# LeftHandPath_Controls.net
KiCad netlist of a schematic drawn in EAGLE
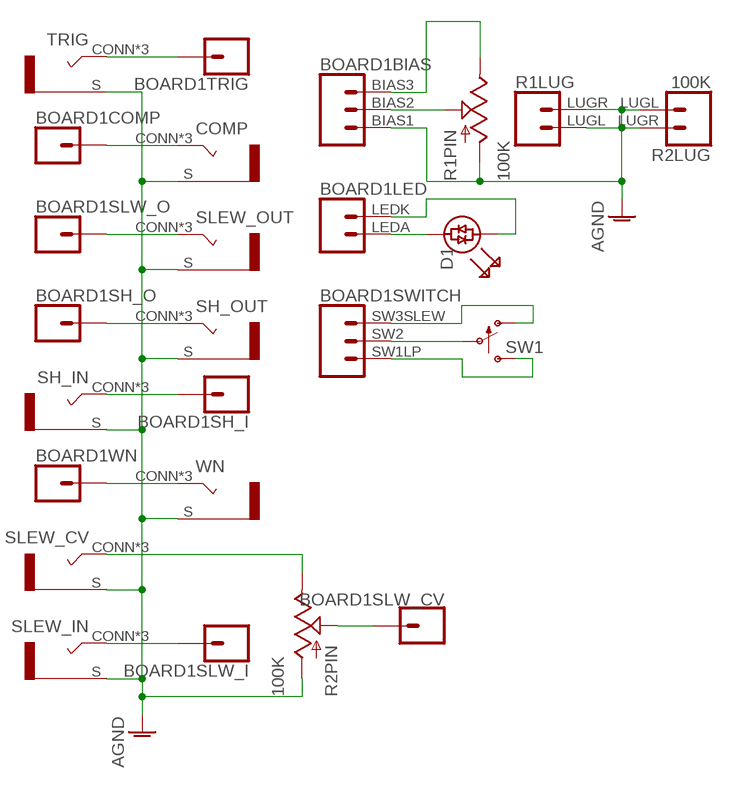
[diagram p0: schematic, sheet 1]

(export (version "E")
  (design (tool "Eeschema 10.0.6"))
  (components
    (comp (ref "BOARD1")
      (value "TLHPFOC_LINK")
      (footprint "eagle-import:TLHPFOC")
      (libsource (lib "eagle-import") (part "TLHPFOC_LINK"))
    )
    (comp (ref "COMP")
      (value "COMBI-JACKCINCHNANA")
      (footprint "eagle-import:NEWCOMBOJACK_PANEL")
      (libsource (lib "eagle-import") (part "COMBI-JACKCINCHNANA"))
    )
    (comp (ref "D1")
      (value "5MM_BICOLOUR_LED")
      (footprint "eagle-import:LED5MM")
      (libsource (lib "eagle-import") (part "5MM_BICOLOUR_LED"))
    )
    (comp (ref "R1")
      (value "100K")
      (footprint "eagle-import:ALPHA_RV09_9MMPOT")
      (libsource (lib "eagle-import") (part "POTENTIOMETER"))
    )
    (comp (ref "R2")
      (value "100K")
      (footprint "eagle-import:ALPHA_RV09_9MMPOT")
      (libsource (lib "eagle-import") (part "POTENTIOMETER"))
    )
    (comp (ref "SH_IN")
      (value "COMBI-JACKCINCHNANA")
      (footprint "eagle-import:NEWCOMBOJACK_PANEL")
      (libsource (lib "eagle-import") (part "COMBI-JACKCINCHNANA"))
    )
    (comp (ref "SH_OUT")
      (value "COMBI-JACKCINCHNANA")
      (footprint "eagle-import:NEWCOMBOJACK_PANEL")
      (libsource (lib "eagle-import") (part "COMBI-JACKCINCHNANA"))
    )
    (comp (ref "SLEW_CV")
      (value "COMBI-JACKCINCHNANA")
      (footprint "eagle-import:NEWCOMBOJACK_PANEL")
      (libsource (lib "eagle-import") (part "COMBI-JACKCINCHNANA"))
    )
    (comp (ref "SLEW_IN")
      (value "COMBI-JACKCINCHNANA")
      (footprint "eagle-import:NEWCOMBOJACK_PANEL")
      (libsource (lib "eagle-import") (part "COMBI-JACKCINCHNANA"))
    )
    (comp (ref "SLEW_OUT")
      (value "COMBI-JACKCINCHNANA")
      (footprint "eagle-import:NEWCOMBOJACK_PANEL")
      (libsource (lib "eagle-import") (part "COMBI-JACKCINCHNANA"))
    )
    (comp (ref "SW1")
      (value "SPDT_SWITCHDW1")
      (footprint "eagle-import:MICRODPDT-DW1")
      (libsource (lib "eagle-import") (part "SPDT_SWITCHDW1"))
    )
    (comp (ref "TRIG")
      (value "COMBI-JACKCINCHNANA")
      (footprint "eagle-import:NEWCOMBOJACK_PANEL")
      (libsource (lib "eagle-import") (part "COMBI-JACKCINCHNANA"))
    )
    (comp (ref "WN")
      (value "COMBI-JACKCINCHNANA")
      (footprint "eagle-import:NEWCOMBOJACK_PANEL")
      (libsource (lib "eagle-import") (part "COMBI-JACKCINCHNANA"))
    )
  )
  (nets
    (net (code "1") (name "AGND") (class "Default")
      (node (ref "BOARD1") (pin "BIAS1") (pinfunction "1_BIAS1") (pintype "passive"))
      (node (ref "COMP") (pin "S") (pinfunction "S_S") (pintype "passive"))
      (node (ref "R1") (pin "C1") (pinfunction "A_C1") (pintype "passive"))
      (node (ref "R1") (pin "LUGL") (pinfunction "1_LUGL") (pintype "passive"))
      (node (ref "R1") (pin "LUGR") (pinfunction "2_LUGR") (pintype "passive"))
      (node (ref "R2") (pin "C1") (pinfunction "A_C1") (pintype "passive"))
      (node (ref "R2") (pin "LUGL") (pinfunction "1_LUGL") (pintype "passive"))
      (node (ref "R2") (pin "LUGR") (pinfunction "2_LUGR") (pintype "passive"))
      (node (ref "SH_IN") (pin "S") (pinfunction "S_S") (pintype "passive"))
      (node (ref "SH_OUT") (pin "S") (pinfunction "S_S") (pintype "passive"))
      (node (ref "SLEW_CV") (pin "S") (pinfunction "S_S") (pintype "passive"))
      (node (ref "SLEW_IN") (pin "S") (pinfunction "S_S") (pintype "passive"))
      (node (ref "SLEW_OUT") (pin "S") (pinfunction "S_S") (pintype "passive"))
      (node (ref "TRIG") (pin "S") (pinfunction "S_S") (pintype "passive"))
      (node (ref "WN") (pin "S") (pinfunction "S_S") (pintype "passive"))
    )
    (net (code "2") (name "Net-(BOARD1A-2)") (class "Default")
      (node (ref "BOARD1") (pin "BIAS2") (pinfunction "2_BIAS2") (pintype "passive"))
      (node (ref "R1") (pin "C2") (pinfunction "W_C2") (pintype "passive"))
    )
    (net (code "3") (name "Net-(BOARD1A-3)") (class "Default")
      (node (ref "BOARD1") (pin "BIAS3") (pinfunction "3_BIAS3") (pintype "passive"))
      (node (ref "R1") (pin "C3") (pinfunction "B_C3") (pintype "passive"))
    )
    (net (code "4") (name "Net-(BOARD1B-1)") (class "Default")
      (node (ref "BOARD1") (pin "COMP") (pinfunction "1_COMP") (pintype "passive"))
      (node (ref "COMP") (pin "CONN") (pinfunction "T_CONN") (pintype "passive"))
      (node (ref "COMP") (pin "T1") (pinfunction "T_T1") (pintype "passive"))
      (node (ref "COMP") (pin "T2") (pinfunction "T_T2") (pintype "passive"))
    )
    (net (code "5") (name "Net-(BOARD1C-1)") (class "Default")
      (node (ref "BOARD1") (pin "LEDA") (pinfunction "1_LEDA") (pintype "passive"))
      (node (ref "D1") (pin "A") (pinfunction "AN_A") (pintype "input"))
    )
    (net (code "6") (name "Net-(BOARD1C-2)") (class "Default")
      (node (ref "BOARD1") (pin "LEDK") (pinfunction "2_LEDK") (pintype "passive"))
      (node (ref "D1") (pin "K") (pinfunction "KA_K") (pintype "output"))
    )
    (net (code "7") (name "Net-(BOARD1D-1)") (class "Default")
      (node (ref "BOARD1") (pin "SH_I") (pinfunction "1_SH_I") (pintype "passive"))
      (node (ref "SH_IN") (pin "CONN") (pinfunction "T_CONN") (pintype "passive"))
      (node (ref "SH_IN") (pin "T1") (pinfunction "T_T1") (pintype "passive"))
      (node (ref "SH_IN") (pin "T2") (pinfunction "T_T2") (pintype "passive"))
    )
    (net (code "8") (name "Net-(BOARD1E-1)") (class "Default")
      (node (ref "BOARD1") (pin "SH_O") (pinfunction "1_SH_O") (pintype "passive"))
      (node (ref "SH_OUT") (pin "CONN") (pinfunction "T_CONN") (pintype "passive"))
      (node (ref "SH_OUT") (pin "T1") (pinfunction "T_T1") (pintype "passive"))
      (node (ref "SH_OUT") (pin "T2") (pinfunction "T_T2") (pintype "passive"))
    )
    (net (code "9") (name "Net-(BOARD1F-1)") (class "Default")
      (node (ref "BOARD1") (pin "SLW_CV") (pinfunction "1_SLW_CV") (pintype "passive"))
      (node (ref "R2") (pin "C2") (pinfunction "W_C2") (pintype "passive"))
    )
    (net (code "10") (name "Net-(BOARD1G-1)") (class "Default")
      (node (ref "BOARD1") (pin "SLW_I") (pinfunction "1_SLW_I") (pintype "passive"))
      (node (ref "SLEW_IN") (pin "CONN") (pinfunction "T_CONN") (pintype "passive"))
      (node (ref "SLEW_IN") (pin "T1") (pinfunction "T_T1") (pintype "passive"))
      (node (ref "SLEW_IN") (pin "T2") (pinfunction "T_T2") (pintype "passive"))
    )
    (net (code "11") (name "Net-(BOARD1H-1)") (class "Default")
      (node (ref "BOARD1") (pin "SLW_O") (pinfunction "1_SLW_O") (pintype "passive"))
      (node (ref "SLEW_OUT") (pin "CONN") (pinfunction "T_CONN") (pintype "passive"))
      (node (ref "SLEW_OUT") (pin "T1") (pinfunction "T_T1") (pintype "passive"))
      (node (ref "SLEW_OUT") (pin "T2") (pinfunction "T_T2") (pintype "passive"))
    )
    (net (code "12") (name "Net-(BOARD1I-1)") (class "Default")
      (node (ref "BOARD1") (pin "SW1LP") (pinfunction "1_SW1LP") (pintype "passive"))
      (node (ref "SW1") (pin "C3") (pinfunction "S_C3") (pintype "passive"))
    )
    (net (code "13") (name "Net-(BOARD1I-2)") (class "Default")
      (node (ref "BOARD1") (pin "SW2") (pinfunction "2_SW2") (pintype "passive"))
      (node (ref "SW1") (pin "C2") (pinfunction "P_C2") (pintype "passive"))
    )
    (net (code "14") (name "Net-(BOARD1I-3)") (class "Default")
      (node (ref "BOARD1") (pin "SW3SLEW") (pinfunction "3_SW3SLEW") (pintype "passive"))
      (node (ref "SW1") (pin "C1") (pinfunction "O_C1") (pintype "passive"))
    )
    (net (code "15") (name "Net-(BOARD1J-1)") (class "Default")
      (node (ref "BOARD1") (pin "TRIG") (pinfunction "1_TRIG") (pintype "passive"))
      (node (ref "TRIG") (pin "CONN") (pinfunction "T_CONN") (pintype "passive"))
      (node (ref "TRIG") (pin "T1") (pinfunction "T_T1") (pintype "passive"))
      (node (ref "TRIG") (pin "T2") (pinfunction "T_T2") (pintype "passive"))
    )
    (net (code "16") (name "Net-(BOARD1K-1)") (class "Default")
      (node (ref "BOARD1") (pin "WN") (pinfunction "1_WN") (pintype "passive"))
      (node (ref "WN") (pin "CONN") (pinfunction "T_CONN") (pintype "passive"))
      (node (ref "WN") (pin "T1") (pinfunction "T_T1") (pintype "passive"))
      (node (ref "WN") (pin "T2") (pinfunction "T_T2") (pintype "passive"))
    )
    (net (code "17") (name "Net-(R2B-B)") (class "Default")
      (node (ref "R2") (pin "C3") (pinfunction "B_C3") (pintype "passive"))
      (node (ref "SLEW_CV") (pin "CONN") (pinfunction "T_CONN") (pintype "passive"))
      (node (ref "SLEW_CV") (pin "T1") (pinfunction "T_T1") (pintype "passive"))
      (node (ref "SLEW_CV") (pin "T2") (pinfunction "T_T2") (pintype "passive"))
    )
  )
)
